# Encoder.net
KiCad netlist of a schematic drawn in Altium Designer
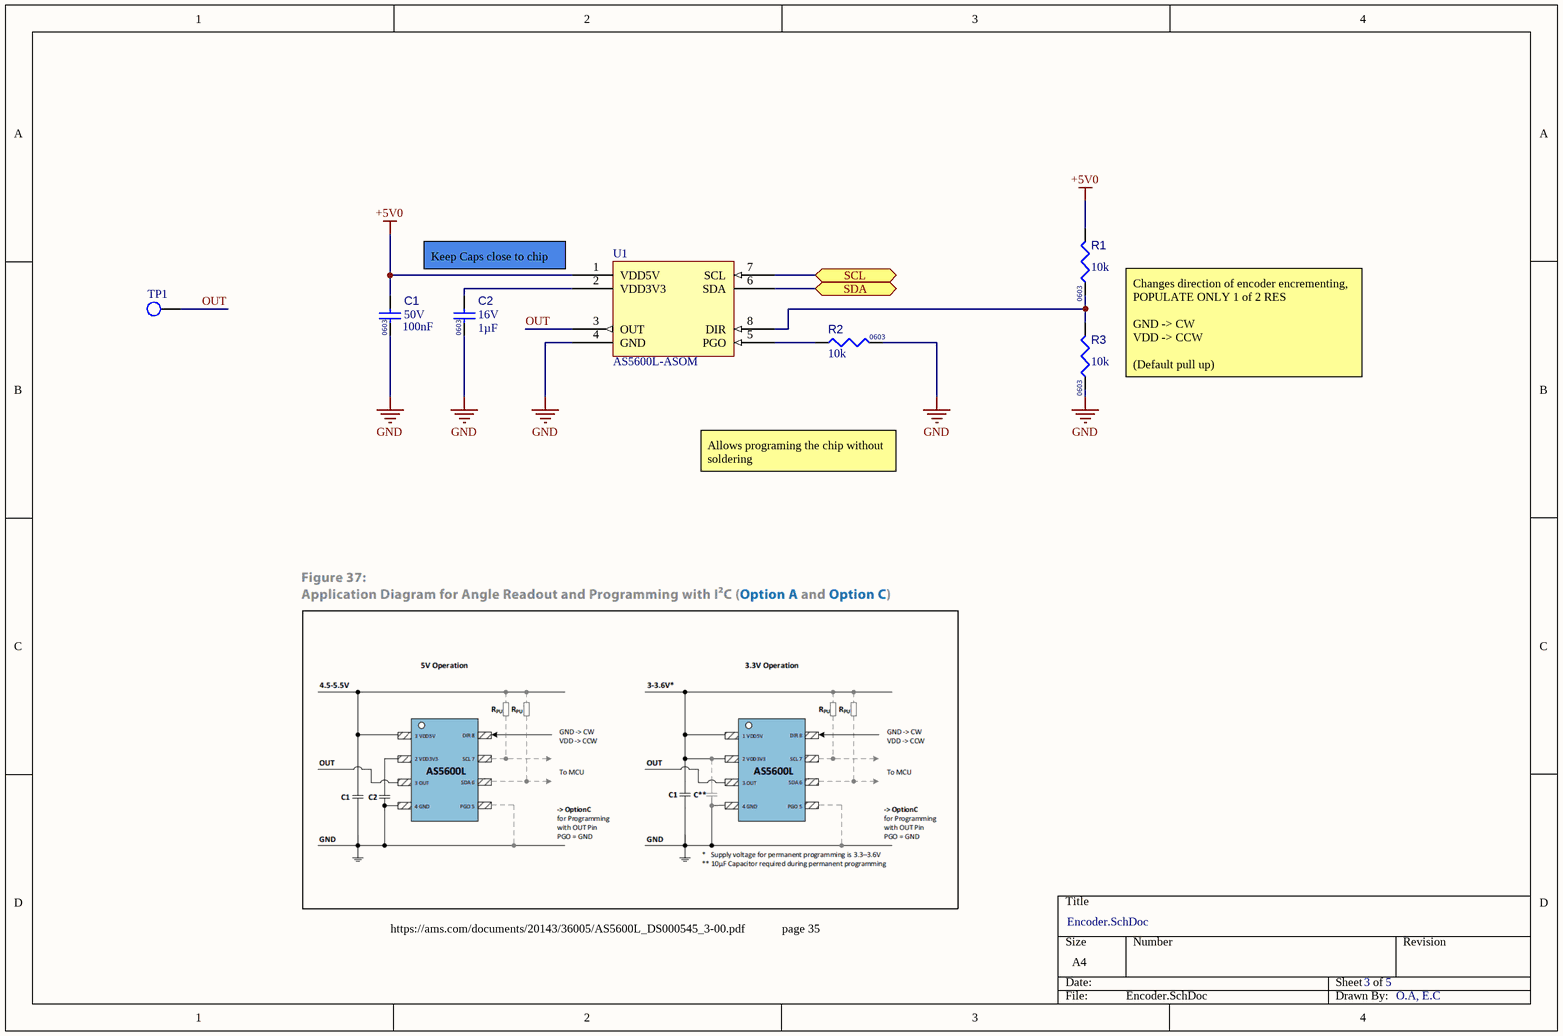
[diagram p0: Encoder.SchDoc]

(export (version "E")
  (design (tool "Eeschema 10.0.6"))
  (components
    (comp (ref "C1")
      (value "100nF")
      (footprint "CAPC1608X90X40NL10T20")
      (description "Chip Capacitor, 100 nF, +/- 10%, 50 V, 0603 (1608 Metric)")
      (fields
        (field (name "TOLERANCE") "10%")
        (field (name "VOLTAGE RATING") "50V")
        (field (name "CASE/PACKAGE") "0603")
        (field (name "Comment") "Capacitor 100 nF +/-10% 50 V 0603")
      )
      (libsource (lib "hawaiirobotics") (part "CAP-NP-2"))
    )
    (comp (ref "C2")
      (value "1µF")
      (footprint "CAPC1608X90X35NL15T15")
      (description "Chip Capacitor, 1 uF, +/- 10%, 16 V, 0603 (1608 Metric)")
      (fields
        (field (name "CASE/PACKAGE") "0603")
        (field (name "VOLTAGE RATING") "16V")
        (field (name "TOLERANCE") "10%")
        (field (name "Comment") "Capacitor 1uF +/- 10% 16V 0603")
      )
      (libsource (lib "hawaiirobotics") (part "CAP-NP-2"))
    )
    (comp (ref "R1")
      (value "10k")
      (footprint "RESC1608X55X25NL10T15")
      (description "Chip Resistor, 10 KOhm, +/- 1%, 01 W, -55 to 155 degC, 0603 (1608 Metric)")
      (fields
        (field (name "CASE/PACKAGE") "0603")
        (field (name "POWER") "100mW")
        (field (name "TOLERANCE") "1%")
      )
      (libsource (lib "hawaiirobotics") (part "RES-2"))
    )
    (comp (ref "R2")
      (value "10k")
      (footprint "RESC1608X55X25NL10T15")
      (description "Chip Resistor, 10 KOhm, +/- 1%, 01 W, -55 to 155 degC, 0603 (1608 Metric)")
      (fields
        (field (name "CASE/PACKAGE") "0603")
        (field (name "POWER") "100mW")
        (field (name "TOLERANCE") "1%")
      )
      (libsource (lib "hawaiirobotics") (part "RES-2"))
    )
    (comp (ref "R3")
      (value "10k")
      (footprint "RESC1608X55X25NL10T15")
      (description "Chip Resistor, 10 KOhm, +/- 1%, 01 W, -55 to 155 degC, 0603 (1608 Metric)")
      (fields
        (field (name "CASE/PACKAGE") "0603")
        (field (name "POWER") "100mW")
        (field (name "TOLERANCE") "1%")
      )
      (libsource (lib "hawaiirobotics") (part "RES-2"))
    )
    (comp (ref "TP1")
      (value "RCUCTE")
      (footprint "FP-S2761-46R-MFG")
      (description "Test point")
      (libsource (lib "hawaiirobotics") (part "RCUCTE-Symbol-1"))
    )
    (comp (ref "U1")
      (value "AS5600L-ASOM")
      (footprint "AS5600L-ASOM-Footprint-1")
      (description "AS5600L Series 12-Bit Programmable On-Axis Magnetic Rotary Position Sensor")
      (libsource (lib "hawaiirobotics") (part "AS5600L-ASOM-Symbol-1"))
    )
  )
  (nets
    (net (code "1") (name "+5V0") (class "Default")
      (node (ref "C1") (pin "2") (pinfunction "2_2") (pintype "passive"))
      (node (ref "R1") (pin "2") (pinfunction "2_2") (pintype "passive"))
      (node (ref "U1") (pin "1") (pinfunction "VDD5V_1") (pintype "power_in"))
    )
    (net (code "2") (name "/OUT") (class "Default")
      (node (ref "TP1") (pin "1") (pinfunction "1_1") (pintype "passive"))
      (node (ref "U1") (pin "3") (pinfunction "OUT_3") (pintype "output"))
    )
    (net (code "3") (name "/SCL") (class "Default")
      (node (ref "U1") (pin "7") (pinfunction "SCL_7") (pintype "input"))
    )
    (net (code "4") (name "/SDA") (class "Default")
      (node (ref "U1") (pin "6") (pinfunction "SDA_6") (pintype "open_collector"))
    )
    (net (code "5") (name "GND") (class "Default")
      (node (ref "C1") (pin "1") (pinfunction "1_1") (pintype "passive"))
      (node (ref "C2") (pin "1") (pinfunction "1_1") (pintype "passive"))
      (node (ref "R2") (pin "2") (pinfunction "2_2") (pintype "passive"))
      (node (ref "R3") (pin "1") (pinfunction "1_1") (pintype "passive"))
      (node (ref "U1") (pin "4") (pinfunction "GND_4") (pintype "power_in"))
    )
    (net (code "6") (name "Net-(U1-DIR)") (class "Default")
      (node (ref "R1") (pin "1") (pinfunction "1_1") (pintype "passive"))
      (node (ref "R3") (pin "2") (pinfunction "2_2") (pintype "passive"))
      (node (ref "U1") (pin "8") (pinfunction "DIR_8") (pintype "input"))
    )
    (net (code "7") (name "Net-(U1-PGO)") (class "Default")
      (node (ref "R2") (pin "1") (pinfunction "1_1") (pintype "passive"))
      (node (ref "U1") (pin "5") (pinfunction "PGO_5") (pintype "input"))
    )
    (net (code "8") (name "Net-(U1-VDD3V3)") (class "Default")
      (node (ref "C2") (pin "2") (pinfunction "2_2") (pintype "passive"))
      (node (ref "U1") (pin "2") (pinfunction "VDD3V3_2") (pintype "power_in"))
    )
  )
)
